# Zio_Qwiic_IR_Thermometer_MLX90614.net
KiCad netlist of a schematic drawn in EAGLE
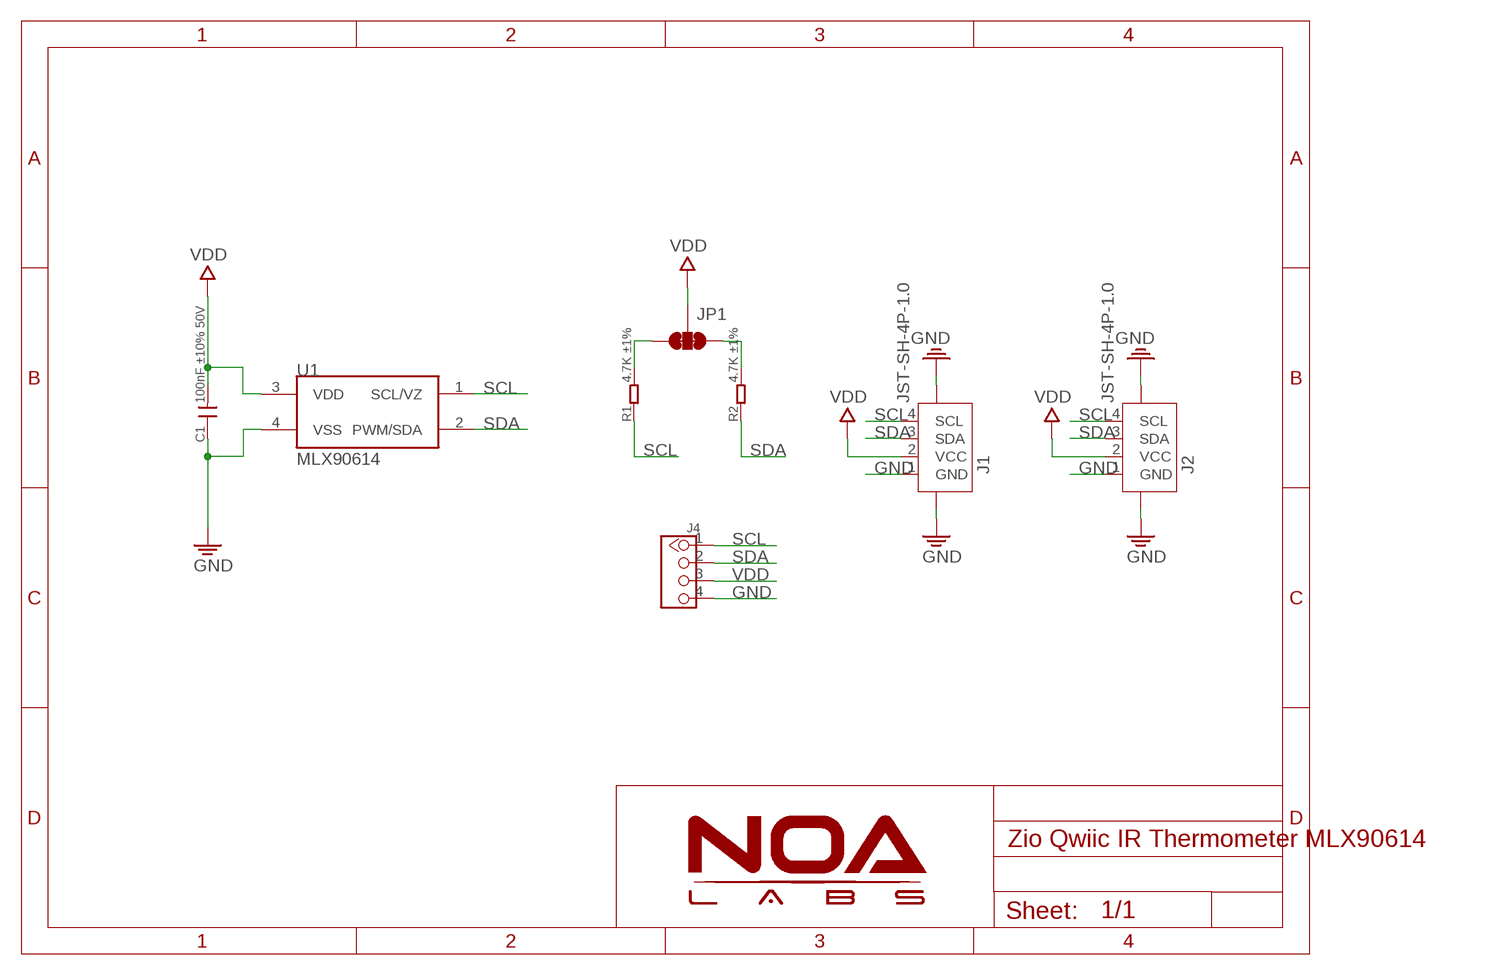
[diagram p0: schematic, sheet 1]

(export (version "E")
  (design (tool "Eeschema 10.0.6"))
  (components
    (comp (ref "C1")
      (value "100nF ±10% 50V")
      (footprint "eagle-import:C0603")
      (libsource (lib "eagle-import") (part "C-0603"))
    )
    (comp (ref "J1")
      (value "JST-SH-4P-1.0")
      (footprint "eagle-import:JST-SH-4P")
      (libsource (lib "eagle-import") (part "JST-SH-4P-1.0"))
    )
    (comp (ref "J2")
      (value "JST-SH-4P-1.0")
      (footprint "eagle-import:JST-SH-4P")
      (libsource (lib "eagle-import") (part "JST-SH-4P-1.0"))
    )
    (comp (ref "J4")
      (value "HEADER-4P-60/35MIL")
      (footprint "eagle-import:4P-65_35MIL")
      (libsource (lib "eagle-import") (part "HEADER-4P-60/35MIL"))
    )
    (comp (ref "JP1")
      (value "SMT-JUMPER_3_2-NC_TRACE")
      (footprint "eagle-import:SMT-JUMPER_3_2-NC_TRACE")
      (libsource (lib "eagle-import") (part "SMT-JUMPER_3_2-NC_TRACE"))
    )
    (comp (ref "R1")
      (value "4.7K ±1%")
      (footprint "eagle-import:R0603")
      (libsource (lib "eagle-import") (part "R-0603"))
    )
    (comp (ref "R2")
      (value "4.7K ±1%")
      (footprint "eagle-import:R0603")
      (libsource (lib "eagle-import") (part "R-0603"))
    )
    (comp (ref "U1")
      (value "MLX90614")
      (footprint "eagle-import:TO-39")
      (libsource (lib "eagle-import") (part "MLX90614"))
    )
  )
  (nets
    (net (code "1") (name "/SCL") (class "Default")
      (node (ref "J1") (pin "4") (pinfunction "SCL_4") (pintype "bidirectional"))
      (node (ref "J2") (pin "4") (pinfunction "SCL_4") (pintype "bidirectional"))
      (node (ref "J4") (pin "1") (pinfunction "P$1_1") (pintype "bidirectional"))
      (node (ref "R1") (pin "1") (pinfunction "1_1") (pintype "passive"))
      (node (ref "U1") (pin "1") (pinfunction "SCL/VZ_1") (pintype "bidirectional"))
    )
    (net (code "2") (name "/SDA") (class "Default")
      (node (ref "J1") (pin "3") (pinfunction "SDA_3") (pintype "bidirectional"))
      (node (ref "J2") (pin "3") (pinfunction "SDA_3") (pintype "bidirectional"))
      (node (ref "J4") (pin "2") (pinfunction "P$2_2") (pintype "bidirectional"))
      (node (ref "R2") (pin "1") (pinfunction "1_1") (pintype "passive"))
      (node (ref "U1") (pin "2") (pinfunction "PWM/SDA_2") (pintype "bidirectional"))
    )
    (net (code "3") (name "GND") (class "Default")
      (node (ref "C1") (pin "1") (pinfunction "1_1") (pintype "passive"))
      (node (ref "J1") (pin "1") (pinfunction "GND_1") (pintype "bidirectional"))
      (node (ref "J1") (pin "NC1") (pinfunction "5_NC1") (pintype "bidirectional"))
      (node (ref "J1") (pin "NC2") (pinfunction "6_NC2") (pintype "bidirectional"))
      (node (ref "J2") (pin "1") (pinfunction "GND_1") (pintype "bidirectional"))
      (node (ref "J2") (pin "NC1") (pinfunction "5_NC1") (pintype "bidirectional"))
      (node (ref "J2") (pin "NC2") (pinfunction "6_NC2") (pintype "bidirectional"))
      (node (ref "J4") (pin "4") (pinfunction "P$4_4") (pintype "bidirectional"))
      (node (ref "U1") (pin "4") (pinfunction "VSS_4") (pintype "bidirectional"))
    )
    (net (code "4") (name "Net-(JP1-Pad1)") (class "Default")
      (node (ref "JP1") (pin "1") (pinfunction "1_1") (pintype "passive"))
      (node (ref "R2") (pin "2") (pinfunction "2_2") (pintype "passive"))
    )
    (net (code "5") (name "Net-(JP1-Pad3)") (class "Default")
      (node (ref "JP1") (pin "3") (pinfunction "3_3") (pintype "passive"))
      (node (ref "R1") (pin "2") (pinfunction "2_2") (pintype "passive"))
    )
    (net (code "6") (name "VDD") (class "Default")
      (node (ref "C1") (pin "2") (pinfunction "2_2") (pintype "passive"))
      (node (ref "J1") (pin "2") (pinfunction "VCC_2") (pintype "bidirectional"))
      (node (ref "J2") (pin "2") (pinfunction "VCC_2") (pintype "bidirectional"))
      (node (ref "J4") (pin "3") (pinfunction "P$3_3") (pintype "bidirectional"))
      (node (ref "JP1") (pin "2") (pinfunction "2_2") (pintype "passive"))
      (node (ref "U1") (pin "3") (pinfunction "VDD_3") (pintype "bidirectional"))
    )
  )
)
